# usb.net
KiCad netlist of a schematic drawn in Altium Designer
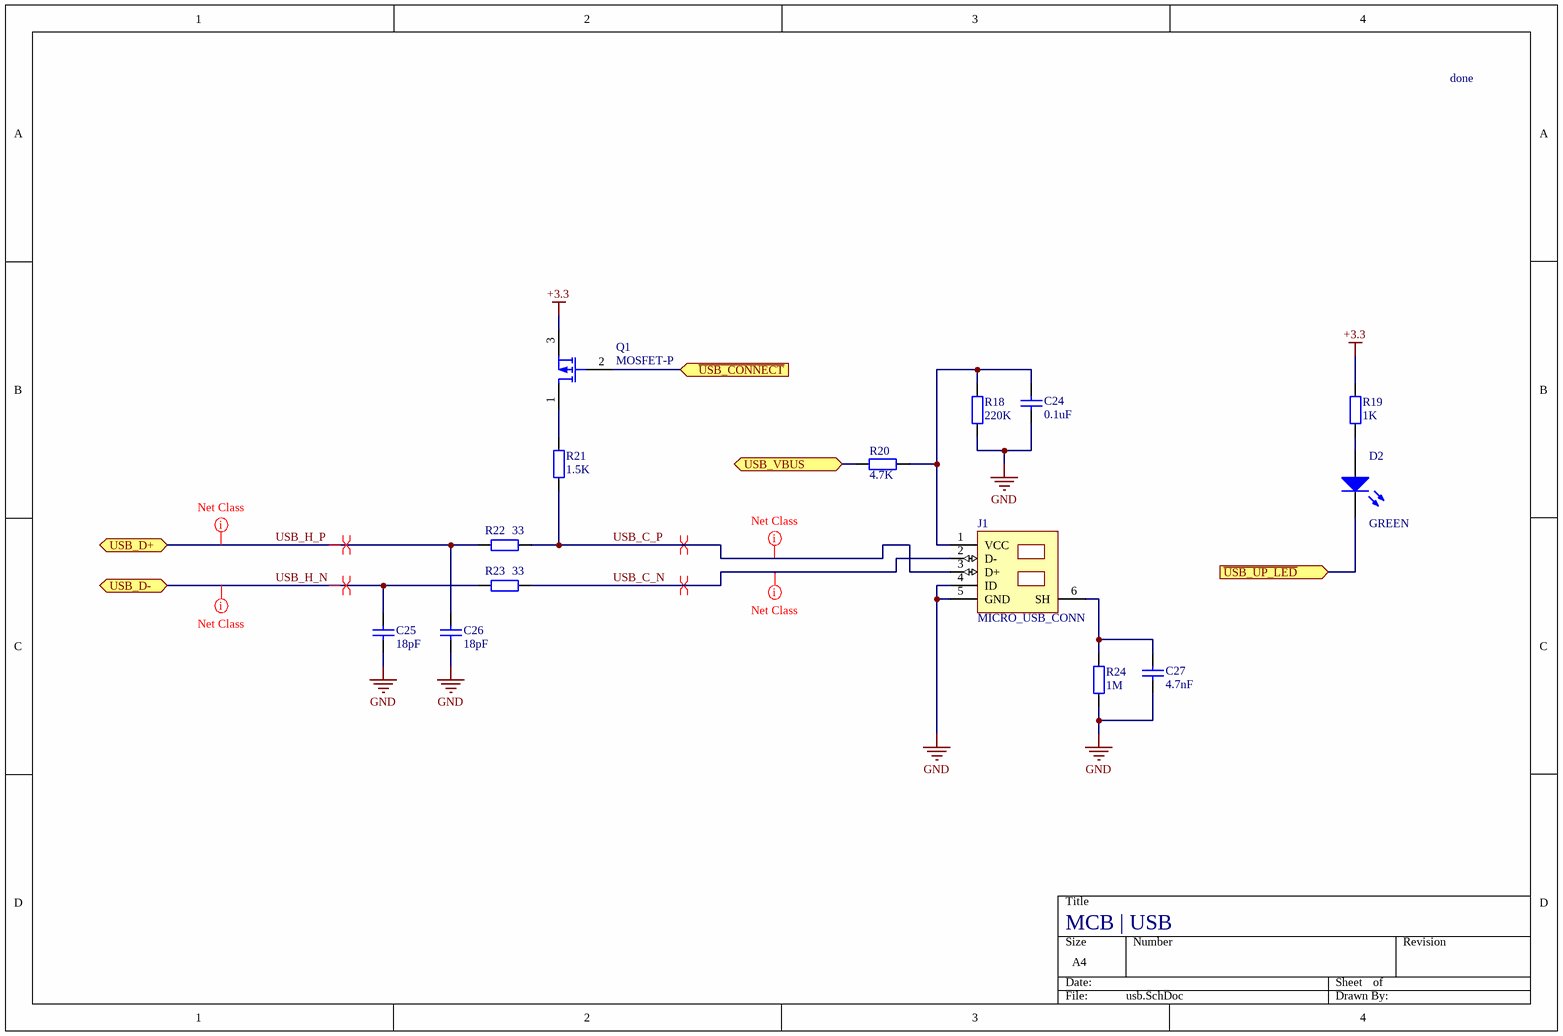
[diagram p0: usb.SchDoc]

(export (version "E")
  (design (tool "Eeschema 10.0.6"))
  (components
    (comp (ref "C24")
      (value "0.1uF")
      (footprint "C0603")
      (description "Capacitor")
      (fields (field (name "Comment") "Cap"))
      (libsource (lib "Miscellaneous Devices") (part "Cap"))
    )
    (comp (ref "C25")
      (value "18pF")
      (footprint "C0603")
      (description "Capacitor")
      (fields (field (name "Comment") "Cap"))
      (libsource (lib "Miscellaneous Devices") (part "Cap"))
    )
    (comp (ref "C26")
      (value "18pF")
      (footprint "C0603")
      (description "Capacitor")
      (fields (field (name "Comment") "Cap"))
      (libsource (lib "Miscellaneous Devices") (part "Cap"))
    )
    (comp (ref "C27")
      (value "4.7nF")
      (footprint "C0603")
      (description "Capacitor")
      (fields (field (name "Comment") "Cap"))
      (libsource (lib "Miscellaneous Devices") (part "Cap"))
    )
    (comp (ref "D2")
      (value "GREEN")
      (footprint "LGQ971")
      (description "Typical RED, GREEN, YELLOW, AMBER GaAs LED")
      (libsource (lib "Miscellaneous Devices") (part "LED2"))
    )
    (comp (ref "J1")
      (value "MICRO_USB_CONN")
      (footprint "USB_MICRO_CONNECTOR")
      (description "MOLEX - 47346-0001 - RECEPTACLE, MICRO USB B, BOTTOM MOUNT")
      (libsource (lib "microUSB") (part "MICRO_USB_CONN"))
    )
    (comp (ref "Q1")
      (value "MOSFET-P")
      (footprint "BSH201,215")
      (description "P-Channel MOSFET")
      (libsource (lib "Miscellaneous Devices") (part "MOSFET-P"))
    )
    (comp (ref "R18")
      (value "220K")
      (footprint "R0603")
      (description "Resistor")
      (fields (field (name "Comment") "Res"))
      (libsource (lib "Miscellaneous Devices") (part "Res2"))
    )
    (comp (ref "R19")
      (value "1K")
      (footprint "R0603")
      (description "Resistor")
      (fields (field (name "Comment") "Res"))
      (libsource (lib "Miscellaneous Devices") (part "Res2"))
    )
    (comp (ref "R20")
      (value "4.7K")
      (footprint "R0603")
      (description "Resistor")
      (fields (field (name "Comment") "Res"))
      (libsource (lib "") (part "Res2_1"))
    )
    (comp (ref "R21")
      (value "1.5K")
      (footprint "R0603")
      (description "Resistor")
      (fields (field (name "Comment") "Res"))
      (libsource (lib "Miscellaneous Devices") (part "Res2"))
    )
    (comp (ref "R22")
      (value "33")
      (footprint "R0603")
      (description "Resistor")
      (fields (field (name "Comment") "Res"))
      (libsource (lib "") (part "Res2_1"))
    )
    (comp (ref "R23")
      (value "33")
      (footprint "R0603")
      (description "Resistor")
      (fields (field (name "Comment") "Res"))
      (libsource (lib "") (part "Res2_1"))
    )
    (comp (ref "R24")
      (value "1M")
      (footprint "R0603")
      (description "Resistor")
      (fields (field (name "Comment") "Res"))
      (libsource (lib "Miscellaneous Devices") (part "Res2"))
    )
  )
  (nets
    (net (code "1") (name "+3.3") (class "Default")
      (node (ref "Q1") (pin "3") (pinfunction "S_3") (pintype "passive"))
      (node (ref "R19") (pin "2") (pinfunction "2_2") (pintype "passive"))
    )
    (net (code "2") (name "/USB_C_N") (class "Default")
      (node (ref "J1") (pin "2") (pinfunction "D-_2") (pintype "bidirectional"))
      (node (ref "R23") (pin "2") (pinfunction "2_2") (pintype "passive"))
    )
    (net (code "3") (name "/USB_C_P") (class "Default")
      (node (ref "J1") (pin "3") (pinfunction "D+_3") (pintype "bidirectional"))
      (node (ref "R21") (pin "1") (pinfunction "1_1") (pintype "passive"))
      (node (ref "R22") (pin "2") (pinfunction "2_2") (pintype "passive"))
    )
    (net (code "4") (name "/USB_H_N") (class "Default")
      (node (ref "C25") (pin "1") (pinfunction "1_1") (pintype "passive"))
      (node (ref "R23") (pin "1") (pinfunction "1_1") (pintype "passive"))
    )
    (net (code "5") (name "/USB_H_P") (class "Default")
      (node (ref "C26") (pin "1") (pinfunction "1_1") (pintype "passive"))
      (node (ref "R22") (pin "1") (pinfunction "1_1") (pintype "passive"))
    )
    (net (code "6") (name "/USB_VBUS") (class "Default")
      (node (ref "R20") (pin "1") (pinfunction "1_1") (pintype "passive"))
    )
    (net (code "7") (name "/~{USB_CONNECT}") (class "Default")
      (node (ref "Q1") (pin "2") (pinfunction "G_2") (pintype "passive"))
    )
    (net (code "8") (name "/~{USB_UP_LED}") (class "Default")
      (node (ref "D2") (pin "2") (pinfunction "K_2") (pintype "passive"))
    )
    (net (code "9") (name "GND") (class "Default")
      (node (ref "C24") (pin "2") (pinfunction "2_2") (pintype "passive"))
      (node (ref "C25") (pin "2") (pinfunction "2_2") (pintype "passive"))
      (node (ref "C26") (pin "2") (pinfunction "2_2") (pintype "passive"))
      (node (ref "C27") (pin "2") (pinfunction "2_2") (pintype "passive"))
      (node (ref "J1") (pin "4") (pinfunction "ID_4") (pintype "passive"))
      (node (ref "J1") (pin "5") (pinfunction "GND_5") (pintype "power_in"))
      (node (ref "R18") (pin "1") (pinfunction "1_1") (pintype "passive"))
      (node (ref "R24") (pin "1") (pinfunction "1_1") (pintype "passive"))
    )
    (net (code "10") (name "Net-(D2-A)") (class "Default")
      (node (ref "D2") (pin "1") (pinfunction "A_1") (pintype "passive"))
      (node (ref "R19") (pin "1") (pinfunction "1_1") (pintype "passive"))
    )
    (net (code "11") (name "Net-(J1-SH)") (class "Default")
      (node (ref "C27") (pin "1") (pinfunction "1_1") (pintype "passive"))
      (node (ref "J1") (pin "6") (pinfunction "SH_6") (pintype "passive"))
      (node (ref "R24") (pin "2") (pinfunction "2_2") (pintype "passive"))
    )
    (net (code "12") (name "Net-(J1-VCC)") (class "Default")
      (node (ref "C24") (pin "1") (pinfunction "1_1") (pintype "passive"))
      (node (ref "J1") (pin "1") (pinfunction "VCC_1") (pintype "power_in"))
      (node (ref "R18") (pin "2") (pinfunction "2_2") (pintype "passive"))
      (node (ref "R20") (pin "2") (pinfunction "2_2") (pintype "passive"))
    )
    (net (code "13") (name "Net-(Q1-D)") (class "Default")
      (node (ref "Q1") (pin "1") (pinfunction "D_1") (pintype "passive"))
      (node (ref "R21") (pin "2") (pinfunction "2_2") (pintype "passive"))
    )
  )
)
